# power-board_LED_V2.net
KiCad netlist of a schematic drawn in EAGLE
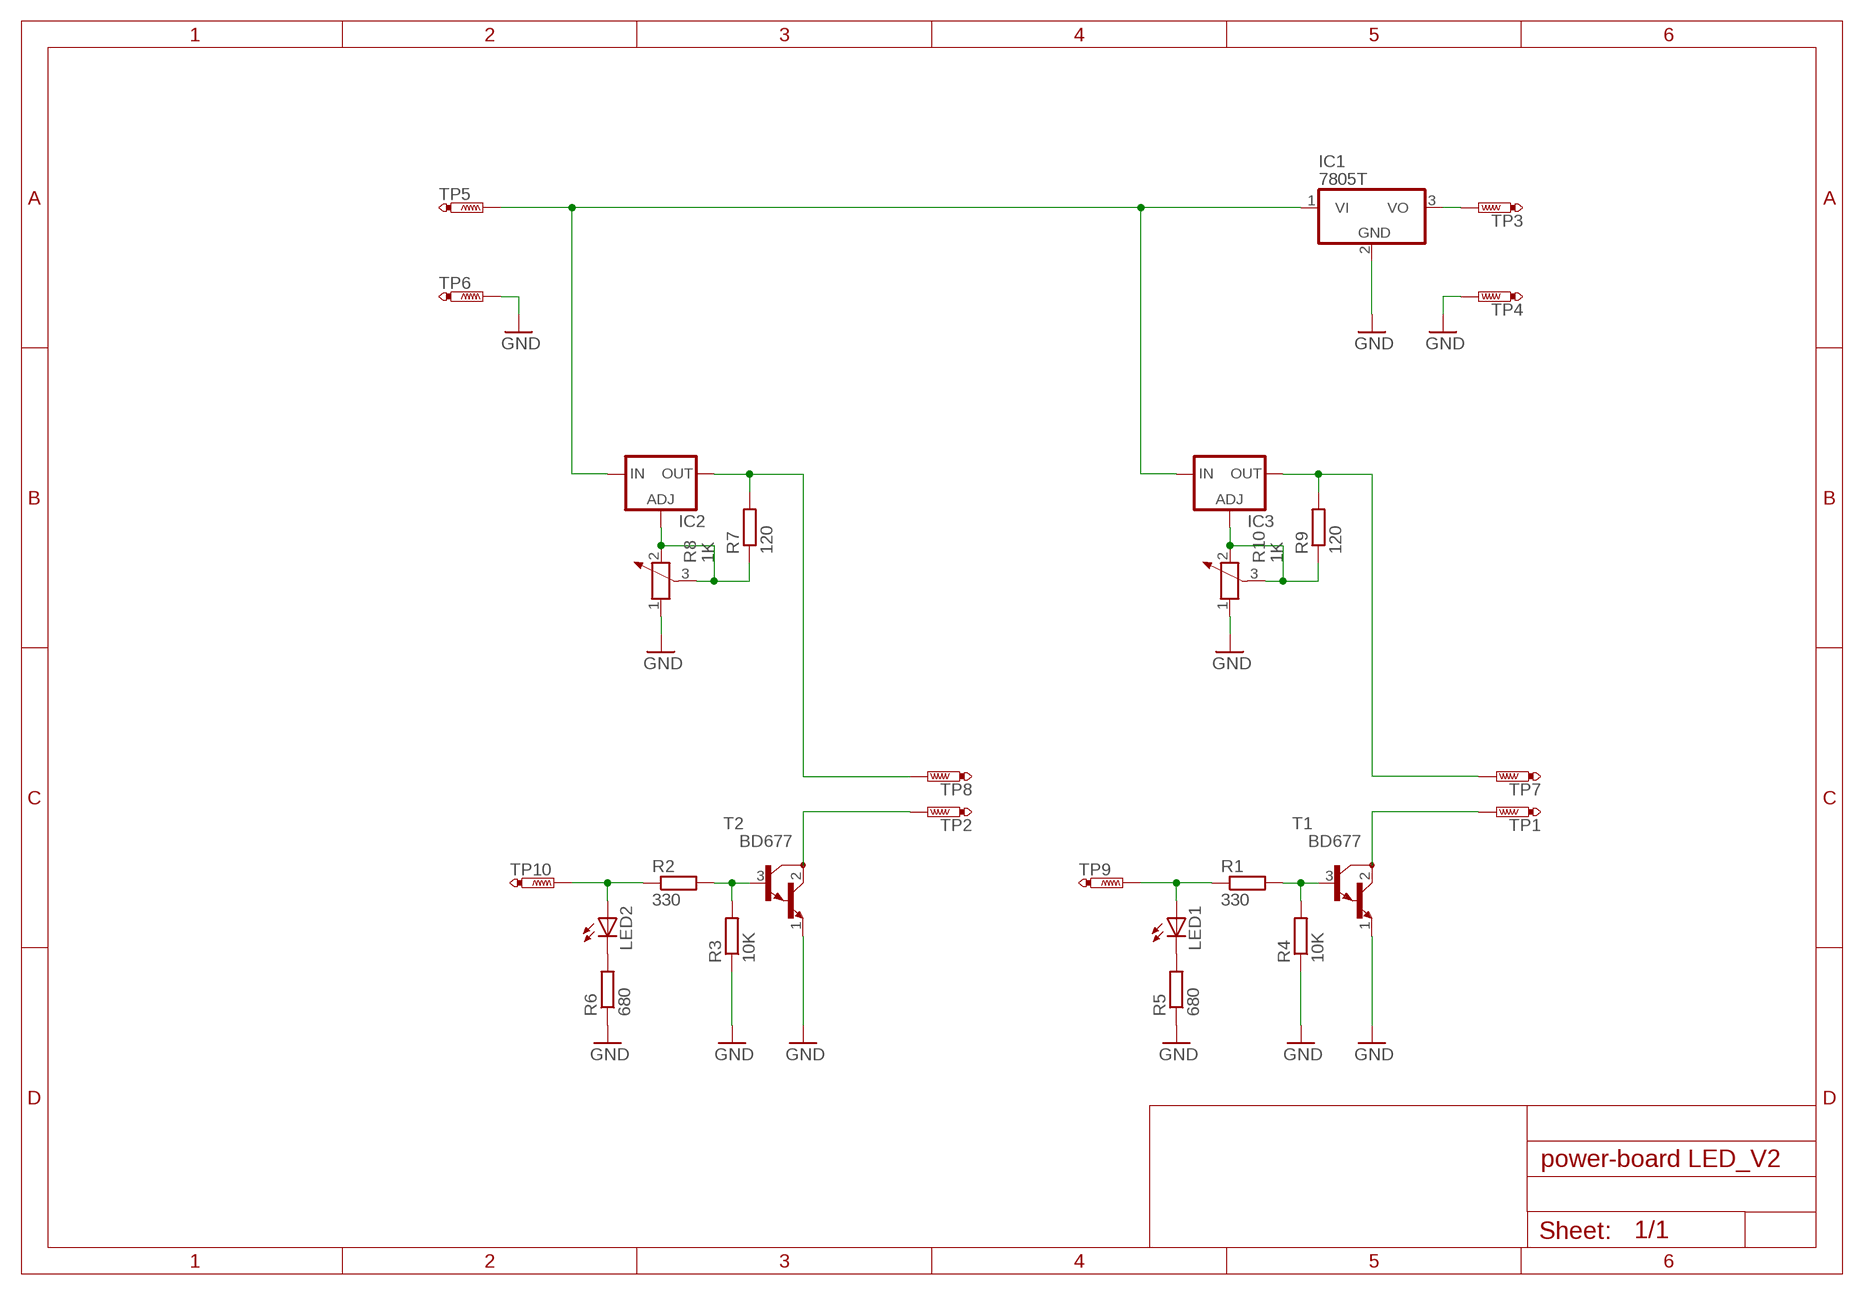
[diagram p0: schematic, sheet 1]

(export (version "E")
  (design (tool "Eeschema 10.0.6"))
  (components
    (comp (ref "IC1")
      (value "7805T")
      (footprint "eagle-import:TO220H")
      (libsource (lib "eagle-import") (part "78T05"))
    )
    (comp (ref "IC2")
      (value "LM317TS")
      (footprint "eagle-import:317TS")
      (libsource (lib "eagle-import") (part "LM317TS"))
    )
    (comp (ref "IC3")
      (value "LM317TS")
      (footprint "eagle-import:317TS")
      (libsource (lib "eagle-import") (part "LM317TS"))
    )
    (comp (ref "LED1")
      (value "LED3MM")
      (footprint "eagle-import:LED3MM")
      (libsource (lib "eagle-import") (part "LED3MM"))
    )
    (comp (ref "LED2")
      (value "LED3MM")
      (footprint "eagle-import:LED3MM")
      (libsource (lib "eagle-import") (part "LED3MM"))
    )
    (comp (ref "R1")
      (value "330")
      (footprint "eagle-import:0207_10")
      (libsource (lib "eagle-import") (part "R-EU_0207/10"))
    )
    (comp (ref "R2")
      (value "330")
      (footprint "eagle-import:0207_10")
      (libsource (lib "eagle-import") (part "R-EU_0207/10"))
    )
    (comp (ref "R3")
      (value "10K")
      (footprint "eagle-import:0207_10")
      (libsource (lib "eagle-import") (part "R-EU_0207/10"))
    )
    (comp (ref "R4")
      (value "10K")
      (footprint "eagle-import:0207_10")
      (libsource (lib "eagle-import") (part "R-EU_0207/10"))
    )
    (comp (ref "R5")
      (value "680")
      (footprint "eagle-import:0207_10")
      (libsource (lib "eagle-import") (part "R-EU_0207/10"))
    )
    (comp (ref "R6")
      (value "680")
      (footprint "eagle-import:0207_10")
      (libsource (lib "eagle-import") (part "R-EU_0207/10"))
    )
    (comp (ref "R7")
      (value "120")
      (footprint "eagle-import:0207_10")
      (libsource (lib "eagle-import") (part "R-EU_0207/10"))
    )
    (comp (ref "R8")
      (value "1K")
      (footprint "eagle-import:PT-10")
      (libsource (lib "eagle-import") (part "POTENTIOMETER_PT-10"))
    )
    (comp (ref "R9")
      (value "120")
      (footprint "eagle-import:0207_10")
      (libsource (lib "eagle-import") (part "R-EU_0207/10"))
    )
    (comp (ref "R10")
      (value "1K")
      (footprint "eagle-import:PT-10")
      (libsource (lib "eagle-import") (part "POTENTIOMETER_PT-10"))
    )
    (comp (ref "T1")
      (value "BD677")
      (footprint "eagle-import:TO126")
      (libsource (lib "eagle-import") (part "BD677"))
    )
    (comp (ref "T2")
      (value "BD677")
      (footprint "eagle-import:TO126")
      (libsource (lib "eagle-import") (part "BD677"))
    )
    (comp (ref "TP1")
      (value "PTR1PAD1-17")
      (footprint "eagle-import:P1-17")
      (libsource (lib "eagle-import") (part "PTR1PAD1-17"))
    )
    (comp (ref "TP2")
      (value "PTR1PAD1-17")
      (footprint "eagle-import:P1-17")
      (libsource (lib "eagle-import") (part "PTR1PAD1-17"))
    )
    (comp (ref "TP3")
      (value "PTR1PAD1-17")
      (footprint "eagle-import:P1-17")
      (libsource (lib "eagle-import") (part "PTR1PAD1-17"))
    )
    (comp (ref "TP4")
      (value "PTR1PAD1-17")
      (footprint "eagle-import:P1-17")
      (libsource (lib "eagle-import") (part "PTR1PAD1-17"))
    )
    (comp (ref "TP5")
      (value "PTR1PAD1-17")
      (footprint "eagle-import:P1-17")
      (libsource (lib "eagle-import") (part "PTR1PAD1-17"))
    )
    (comp (ref "TP6")
      (value "PTR1PAD1-17")
      (footprint "eagle-import:P1-17")
      (libsource (lib "eagle-import") (part "PTR1PAD1-17"))
    )
    (comp (ref "TP7")
      (value "PTR1PAD1-17")
      (footprint "eagle-import:P1-17")
      (libsource (lib "eagle-import") (part "PTR1PAD1-17"))
    )
    (comp (ref "TP8")
      (value "PTR1PAD1-17")
      (footprint "eagle-import:P1-17")
      (libsource (lib "eagle-import") (part "PTR1PAD1-17"))
    )
    (comp (ref "TP9")
      (value "PTR1PAD1-17")
      (footprint "eagle-import:P1-17")
      (libsource (lib "eagle-import") (part "PTR1PAD1-17"))
    )
    (comp (ref "TP10")
      (value "PTR1PAD1-17")
      (footprint "eagle-import:P1-17")
      (libsource (lib "eagle-import") (part "PTR1PAD1-17"))
    )
  )
  (nets
    (net (code "1") (name "GND") (class "Default")
      (node (ref "IC1") (pin "2") (pinfunction "GND_2") (pintype "passive"))
      (node (ref "R10") (pin "1") (pinfunction "1_1") (pintype "passive"))
      (node (ref "R3") (pin "1") (pinfunction "1_1") (pintype "passive"))
      (node (ref "R4") (pin "1") (pinfunction "1_1") (pintype "passive"))
      (node (ref "R5") (pin "1") (pinfunction "1_1") (pintype "passive"))
      (node (ref "R6") (pin "1") (pinfunction "1_1") (pintype "passive"))
      (node (ref "R8") (pin "1") (pinfunction "1_1") (pintype "passive"))
      (node (ref "T1") (pin "1") (pinfunction "E_1") (pintype "passive"))
      (node (ref "T2") (pin "1") (pinfunction "E_1") (pintype "passive"))
      (node (ref "TP4") (pin "TP") (pinfunction "TP_TP") (pintype "input"))
      (node (ref "TP6") (pin "TP") (pinfunction "TP_TP") (pintype "input"))
    )
    (net (code "2") (name "Net-(IC1-VI)") (class "Default")
      (node (ref "IC1") (pin "1") (pinfunction "VI_1") (pintype "input"))
      (node (ref "IC2") (pin "3") (pinfunction "IN_3") (pintype "input"))
      (node (ref "IC3") (pin "3") (pinfunction "IN_3") (pintype "input"))
      (node (ref "TP5") (pin "TP") (pinfunction "TP_TP") (pintype "input"))
    )
    (net (code "3") (name "Net-(IC1-VO)") (class "Default")
      (node (ref "IC1") (pin "3") (pinfunction "VO_3") (pintype "passive"))
      (node (ref "TP3") (pin "TP") (pinfunction "TP_TP") (pintype "input"))
    )
    (net (code "4") (name "Net-(IC2-ADJ)") (class "Default")
      (node (ref "IC2") (pin "1") (pinfunction "ADJ_1") (pintype "input"))
      (node (ref "R7") (pin "1") (pinfunction "1_1") (pintype "passive"))
      (node (ref "R8") (pin "2") (pinfunction "2_2") (pintype "passive"))
      (node (ref "R8") (pin "3") (pinfunction "3_3") (pintype "passive"))
    )
    (net (code "5") (name "Net-(IC2-OUT)") (class "Default")
      (node (ref "IC2") (pin "2") (pinfunction "OUT_2") (pintype "passive"))
      (node (ref "R7") (pin "2") (pinfunction "2_2") (pintype "passive"))
      (node (ref "TP8") (pin "TP") (pinfunction "TP_TP") (pintype "input"))
    )
    (net (code "6") (name "Net-(IC3-ADJ)") (class "Default")
      (node (ref "IC3") (pin "1") (pinfunction "ADJ_1") (pintype "input"))
      (node (ref "R10") (pin "2") (pinfunction "2_2") (pintype "passive"))
      (node (ref "R10") (pin "3") (pinfunction "3_3") (pintype "passive"))
      (node (ref "R9") (pin "1") (pinfunction "1_1") (pintype "passive"))
    )
    (net (code "7") (name "Net-(IC3-OUT)") (class "Default")
      (node (ref "IC3") (pin "2") (pinfunction "OUT_2") (pintype "passive"))
      (node (ref "R9") (pin "2") (pinfunction "2_2") (pintype "passive"))
      (node (ref "TP7") (pin "TP") (pinfunction "TP_TP") (pintype "input"))
    )
    (net (code "8") (name "Net-(LED1-C)") (class "Default")
      (node (ref "LED1") (pin "K") (pinfunction "C_K") (pintype "passive"))
      (node (ref "R5") (pin "2") (pinfunction "2_2") (pintype "passive"))
    )
    (net (code "9") (name "Net-(LED1-PadA)") (class "Default")
      (node (ref "LED1") (pin "A") (pinfunction "A_A") (pintype "passive"))
      (node (ref "R1") (pin "1") (pinfunction "1_1") (pintype "passive"))
      (node (ref "TP9") (pin "TP") (pinfunction "TP_TP") (pintype "input"))
    )
    (net (code "10") (name "Net-(LED2-C)") (class "Default")
      (node (ref "LED2") (pin "K") (pinfunction "C_K") (pintype "passive"))
      (node (ref "R6") (pin "2") (pinfunction "2_2") (pintype "passive"))
    )
    (net (code "11") (name "Net-(LED2-PadA)") (class "Default")
      (node (ref "LED2") (pin "A") (pinfunction "A_A") (pintype "passive"))
      (node (ref "R2") (pin "1") (pinfunction "1_1") (pintype "passive"))
      (node (ref "TP10") (pin "TP") (pinfunction "TP_TP") (pintype "input"))
    )
    (net (code "12") (name "Net-(T1-B)") (class "Default")
      (node (ref "R1") (pin "2") (pinfunction "2_2") (pintype "passive"))
      (node (ref "R4") (pin "2") (pinfunction "2_2") (pintype "passive"))
      (node (ref "T1") (pin "3") (pinfunction "B_3") (pintype "passive"))
    )
    (net (code "13") (name "Net-(T1-C)") (class "Default")
      (node (ref "T1") (pin "2") (pinfunction "C_2") (pintype "passive"))
      (node (ref "TP1") (pin "TP") (pinfunction "TP_TP") (pintype "input"))
    )
    (net (code "14") (name "Net-(T2-B)") (class "Default")
      (node (ref "R2") (pin "2") (pinfunction "2_2") (pintype "passive"))
      (node (ref "R3") (pin "2") (pinfunction "2_2") (pintype "passive"))
      (node (ref "T2") (pin "3") (pinfunction "B_3") (pintype "passive"))
    )
    (net (code "15") (name "Net-(T2-C)") (class "Default")
      (node (ref "T2") (pin "2") (pinfunction "C_2") (pintype "passive"))
      (node (ref "TP2") (pin "TP") (pinfunction "TP_TP") (pintype "input"))
    )
  )
)
